# vcf-diode-ladder.net
KiCad netlist of a schematic drawn in EAGLE
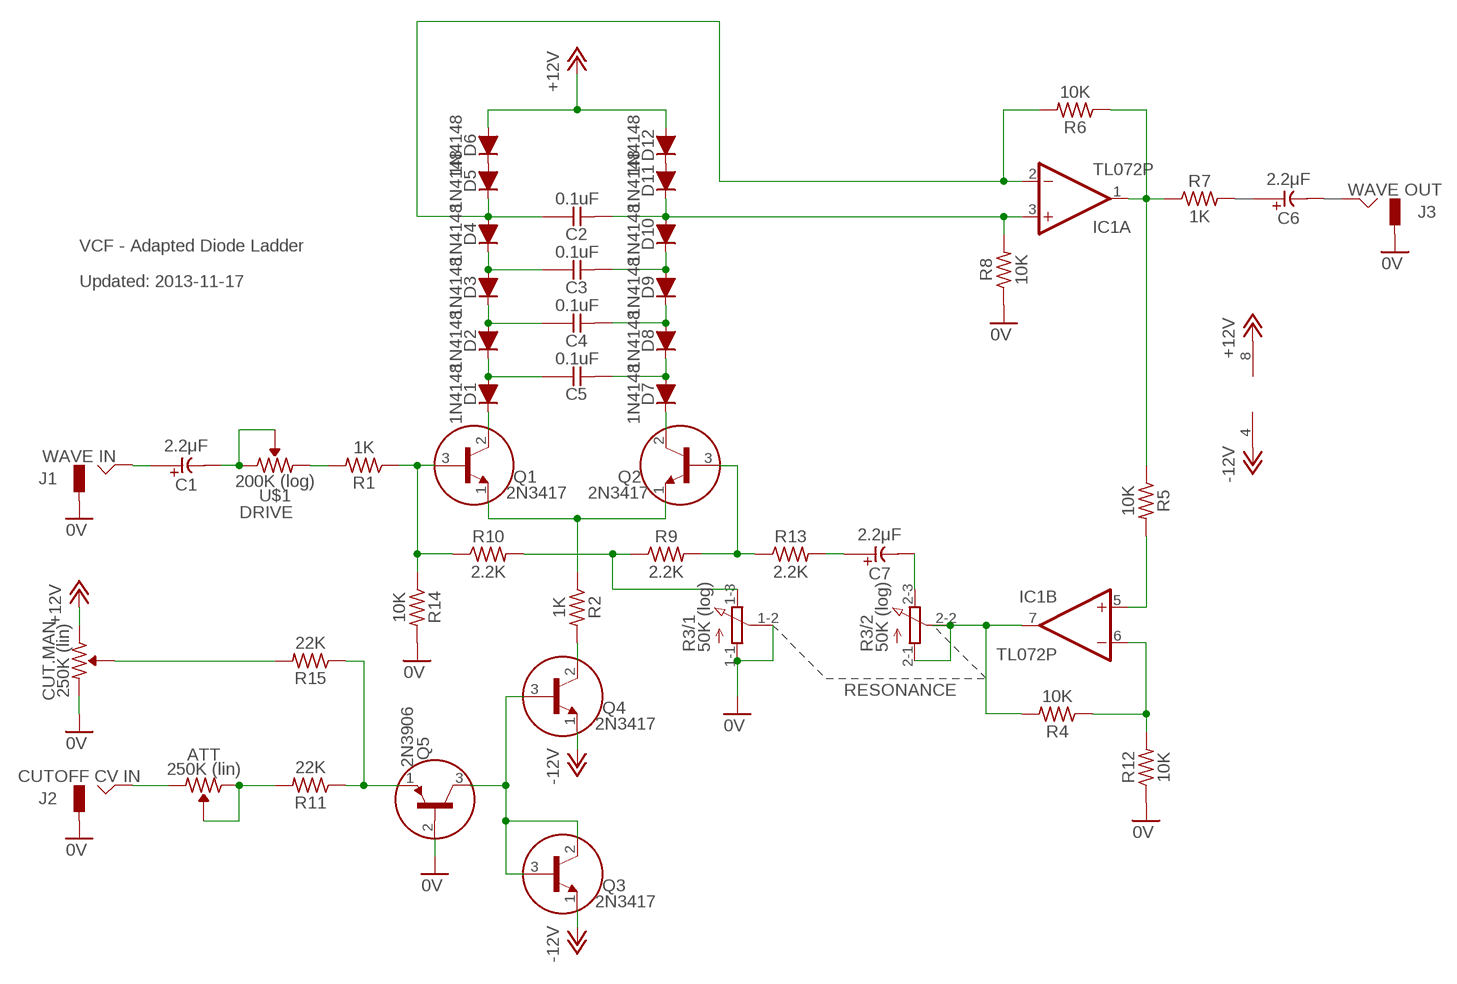
[diagram p0: schematic, sheet 1]

(export (version "E")
  (design (tool "Eeschema 10.0.6"))
  (components
    (comp (ref "ATT")
      (value "250K (lin)")
      (footprint "eagle-import:R-VAR")
      (libsource (lib "eagle-import") (part "R-VAR"))
    )
    (comp (ref "C1")
      (value "2.2μF")
      (footprint "eagle-import:E2-5")
      (libsource (lib "eagle-import") (part "CE-USE2-5"))
    )
    (comp (ref "C2")
      (value "0.1uF")
      (footprint "eagle-import:C025-024X044")
      (libsource (lib "eagle-import") (part "CC-US025-024X044"))
    )
    (comp (ref "C3")
      (value "0.1uF")
      (footprint "eagle-import:C025-024X044")
      (libsource (lib "eagle-import") (part "CC-US025-024X044"))
    )
    (comp (ref "C4")
      (value "0.1uF")
      (footprint "eagle-import:C025-024X044")
      (libsource (lib "eagle-import") (part "CC-US025-024X044"))
    )
    (comp (ref "C5")
      (value "0.1uF")
      (footprint "eagle-import:C025-024X044")
      (libsource (lib "eagle-import") (part "CC-US025-024X044"))
    )
    (comp (ref "C6")
      (value "2.2μF")
      (footprint "eagle-import:E2-5")
      (libsource (lib "eagle-import") (part "CE-USE2-5"))
    )
    (comp (ref "C7")
      (value "2.2μF")
      (footprint "eagle-import:E2-5")
      (libsource (lib "eagle-import") (part "CE-USE2-5"))
    )
    (comp (ref "CUT.MAN")
      (value "250K (lin)")
      (footprint "eagle-import:R-VAR")
      (libsource (lib "eagle-import") (part "R-VAR"))
    )
    (comp (ref "D1")
      (value "1N4148")
      (footprint "eagle-import:DO35-7")
      (libsource (lib "eagle-import") (part "1N4148"))
    )
    (comp (ref "D2")
      (value "1N4148")
      (footprint "eagle-import:DO35-7")
      (libsource (lib "eagle-import") (part "1N4148"))
    )
    (comp (ref "D3")
      (value "1N4148")
      (footprint "eagle-import:DO35-7")
      (libsource (lib "eagle-import") (part "1N4148"))
    )
    (comp (ref "D4")
      (value "1N4148")
      (footprint "eagle-import:DO35-7")
      (libsource (lib "eagle-import") (part "1N4148"))
    )
    (comp (ref "D5")
      (value "1N4148")
      (footprint "eagle-import:DO35-7")
      (libsource (lib "eagle-import") (part "1N4148"))
    )
    (comp (ref "D6")
      (value "1N4148")
      (footprint "eagle-import:DO35-7")
      (libsource (lib "eagle-import") (part "1N4148"))
    )
    (comp (ref "D7")
      (value "1N4148")
      (footprint "eagle-import:DO35-7")
      (libsource (lib "eagle-import") (part "1N4148"))
    )
    (comp (ref "D8")
      (value "1N4148")
      (footprint "eagle-import:DO35-7")
      (libsource (lib "eagle-import") (part "1N4148"))
    )
    (comp (ref "D9")
      (value "1N4148")
      (footprint "eagle-import:DO35-7")
      (libsource (lib "eagle-import") (part "1N4148"))
    )
    (comp (ref "D10")
      (value "1N4148")
      (footprint "eagle-import:DO35-7")
      (libsource (lib "eagle-import") (part "1N4148"))
    )
    (comp (ref "D11")
      (value "1N4148")
      (footprint "eagle-import:DO35-7")
      (libsource (lib "eagle-import") (part "1N4148"))
    )
    (comp (ref "D12")
      (value "1N4148")
      (footprint "eagle-import:DO35-7")
      (libsource (lib "eagle-import") (part "1N4148"))
    )
    (comp (ref "IC1")
      (value "TL072P")
      (footprint "eagle-import:DIL08")
      (libsource (lib "eagle-import") (part "TL072P"))
    )
    (comp (ref "J1")
      (value "WAVE IN")
      (footprint "eagle-import:JACK-M")
      (libsource (lib "eagle-import") (part "JACK-M"))
    )
    (comp (ref "J2")
      (value "CUTOFF CV IN")
      (footprint "eagle-import:JACK-M")
      (libsource (lib "eagle-import") (part "JACK-M"))
    )
    (comp (ref "J3")
      (value "WAVE OUT")
      (footprint "eagle-import:JACK-M")
      (libsource (lib "eagle-import") (part "JACK-M"))
    )
    (comp (ref "Q1")
      (value "2N3417")
      (footprint "eagle-import:TO92")
      (libsource (lib "eagle-import") (part "2N3417"))
    )
    (comp (ref "Q2")
      (value "2N3417")
      (footprint "eagle-import:TO92")
      (libsource (lib "eagle-import") (part "2N3417"))
    )
    (comp (ref "Q3")
      (value "2N3417")
      (footprint "eagle-import:TO92")
      (libsource (lib "eagle-import") (part "2N3417"))
    )
    (comp (ref "Q4")
      (value "2N3417")
      (footprint "eagle-import:TO92")
      (libsource (lib "eagle-import") (part "2N3417"))
    )
    (comp (ref "Q5")
      (value "2N3906")
      (footprint "eagle-import:TO92")
      (libsource (lib "eagle-import") (part "2N3906"))
    )
    (comp (ref "R1")
      (value "1K")
      (footprint "eagle-import:0309_10")
      (libsource (lib "eagle-import") (part "R0309/10"))
    )
    (comp (ref "R2")
      (value "1K")
      (footprint "eagle-import:0309_10")
      (libsource (lib "eagle-import") (part "R0309/10"))
    )
    (comp (ref "R3")
      (value "50K (log)")
      (footprint "eagle-import:3RP_1610G")
      (libsource (lib "eagle-import") (part "3RP/1610G"))
    )
    (comp (ref "R4")
      (value "10K")
      (footprint "eagle-import:0309_10")
      (libsource (lib "eagle-import") (part "R0309/10"))
    )
    (comp (ref "R5")
      (value "10K")
      (footprint "eagle-import:0309_10")
      (libsource (lib "eagle-import") (part "R0309/10"))
    )
    (comp (ref "R6")
      (value "10K")
      (footprint "eagle-import:0309_10")
      (libsource (lib "eagle-import") (part "R0309/10"))
    )
    (comp (ref "R7")
      (value "1K")
      (footprint "eagle-import:0309_10")
      (libsource (lib "eagle-import") (part "R0309/10"))
    )
    (comp (ref "R8")
      (value "10K")
      (footprint "eagle-import:0309_10")
      (libsource (lib "eagle-import") (part "R0309/10"))
    )
    (comp (ref "R9")
      (value "2.2K")
      (footprint "eagle-import:0309_10")
      (libsource (lib "eagle-import") (part "R0309/10"))
    )
    (comp (ref "R10")
      (value "2.2K")
      (footprint "eagle-import:0309_10")
      (libsource (lib "eagle-import") (part "R0309/10"))
    )
    (comp (ref "R11")
      (value "22K")
      (footprint "eagle-import:0309_10")
      (libsource (lib "eagle-import") (part "R0309/10"))
    )
    (comp (ref "R12")
      (value "10K")
      (footprint "eagle-import:0309_10")
      (libsource (lib "eagle-import") (part "R0309/10"))
    )
    (comp (ref "R13")
      (value "2.2K")
      (footprint "eagle-import:0309_10")
      (libsource (lib "eagle-import") (part "R0309/10"))
    )
    (comp (ref "R14")
      (value "10K")
      (footprint "eagle-import:0309_10")
      (libsource (lib "eagle-import") (part "R0309/10"))
    )
    (comp (ref "R15")
      (value "22K")
      (footprint "eagle-import:0309_10")
      (libsource (lib "eagle-import") (part "R0309/10"))
    )
    (comp (ref "U$1")
      (value "200K (log)")
      (footprint "eagle-import:R-VAR")
      (libsource (lib "eagle-import") (part "R-VAR"))
    )
  )
  (nets
    (net (code "1") (name "+12V") (class "Default")
      (node (ref "CUT.MAN") (pin "R1") (pinfunction "1_R1") (pintype "passive"))
      (node (ref "D12") (pin "A") (pinfunction "A_A") (pintype "passive"))
      (node (ref "D6") (pin "A") (pinfunction "A_A") (pintype "passive"))
      (node (ref "IC1") (pin "8") (pinfunction "V+_8") (pintype "power_in"))
    )
    (net (code "2") (name "-12V") (class "Default")
      (node (ref "IC1") (pin "4") (pinfunction "V-_4") (pintype "power_in"))
      (node (ref "Q3") (pin "1") (pinfunction "E_1") (pintype "passive"))
      (node (ref "Q4") (pin "1") (pinfunction "E_1") (pintype "passive"))
    )
    (net (code "3") (name "0V") (class "Default")
      (node (ref "CUT.MAN") (pin "R2") (pinfunction "2_R2") (pintype "passive"))
      (node (ref "J1") (pin "GND") (pinfunction "GND_GND") (pintype "bidirectional"))
      (node (ref "J2") (pin "GND") (pinfunction "GND_GND") (pintype "bidirectional"))
      (node (ref "J3") (pin "GND") (pinfunction "GND_GND") (pintype "bidirectional"))
      (node (ref "Q5") (pin "2") (pinfunction "B_2") (pintype "passive"))
      (node (ref "R12") (pin "1") (pinfunction "1_1") (pintype "passive"))
      (node (ref "R14") (pin "2") (pinfunction "2_2") (pintype "passive"))
      (node (ref "R3") (pin "1-1") (pinfunction "A_1-1") (pintype "passive"))
      (node (ref "R3") (pin "1-2") (pinfunction "S_1-2") (pintype "passive"))
      (node (ref "R8") (pin "1") (pinfunction "1_1") (pintype "passive"))
    )
    (net (code "4") (name "Net-(ATT-1)") (class "Default")
      (node (ref "ATT") (pin "R1") (pinfunction "1_R1") (pintype "passive"))
      (node (ref "ATT") (pin "VAR") (pinfunction "P$1_VAR") (pintype "passive"))
      (node (ref "R11") (pin "2") (pinfunction "2_2") (pintype "passive"))
    )
    (net (code "5") (name "Net-(ATT-2)") (class "Default")
      (node (ref "ATT") (pin "R2") (pinfunction "2_R2") (pintype "passive"))
      (node (ref "J2") (pin "HOT") (pinfunction "HOT_HOT") (pintype "bidirectional"))
    )
    (net (code "6") (name "Net-(C1-Pad+)") (class "Default")
      (node (ref "C1") (pin "+") (pinfunction "+_+") (pintype "passive"))
      (node (ref "J1") (pin "HOT") (pinfunction "HOT_HOT") (pintype "bidirectional"))
    )
    (net (code "7") (name "Net-(C3-Pad1)") (class "Default")
      (node (ref "C3") (pin "1") (pinfunction "1_1") (pintype "passive"))
      (node (ref "D3") (pin "A") (pinfunction "A_A") (pintype "passive"))
      (node (ref "D4") (pin "C") (pinfunction "C_C") (pintype "passive"))
    )
    (net (code "8") (name "Net-(C3-Pad2)") (class "Default")
      (node (ref "C3") (pin "2") (pinfunction "2_2") (pintype "passive"))
      (node (ref "D10") (pin "C") (pinfunction "C_C") (pintype "passive"))
      (node (ref "D9") (pin "A") (pinfunction "A_A") (pintype "passive"))
    )
    (net (code "9") (name "Net-(C4-Pad1)") (class "Default")
      (node (ref "C4") (pin "1") (pinfunction "1_1") (pintype "passive"))
      (node (ref "D2") (pin "A") (pinfunction "A_A") (pintype "passive"))
      (node (ref "D3") (pin "C") (pinfunction "C_C") (pintype "passive"))
    )
    (net (code "10") (name "Net-(C4-Pad2)") (class "Default")
      (node (ref "C4") (pin "2") (pinfunction "2_2") (pintype "passive"))
      (node (ref "D8") (pin "A") (pinfunction "A_A") (pintype "passive"))
      (node (ref "D9") (pin "C") (pinfunction "C_C") (pintype "passive"))
    )
    (net (code "11") (name "Net-(C5-Pad1)") (class "Default")
      (node (ref "C5") (pin "1") (pinfunction "1_1") (pintype "passive"))
      (node (ref "D1") (pin "A") (pinfunction "A_A") (pintype "passive"))
      (node (ref "D2") (pin "C") (pinfunction "C_C") (pintype "passive"))
    )
    (net (code "12") (name "Net-(C5-Pad2)") (class "Default")
      (node (ref "C5") (pin "2") (pinfunction "2_2") (pintype "passive"))
      (node (ref "D7") (pin "A") (pinfunction "A_A") (pintype "passive"))
      (node (ref "D8") (pin "C") (pinfunction "C_C") (pintype "passive"))
    )
    (net (code "13") (name "Net-(C7-Pad+)") (class "Default")
      (node (ref "C7") (pin "+") (pinfunction "+_+") (pintype "passive"))
      (node (ref "R13") (pin "2") (pinfunction "2_2") (pintype "passive"))
    )
    (net (code "14") (name "Net-(CUT.MAN-P$1)") (class "Default")
      (node (ref "CUT.MAN") (pin "VAR") (pinfunction "P$1_VAR") (pintype "passive"))
      (node (ref "R15") (pin "2") (pinfunction "2_2") (pintype "passive"))
    )
    (net (code "15") (name "Net-(D5-PadA)") (class "Default")
      (node (ref "D5") (pin "A") (pinfunction "A_A") (pintype "passive"))
      (node (ref "D6") (pin "C") (pinfunction "C_C") (pintype "passive"))
    )
    (net (code "16") (name "Net-(D11-PadA)") (class "Default")
      (node (ref "D11") (pin "A") (pinfunction "A_A") (pintype "passive"))
      (node (ref "D12") (pin "C") (pinfunction "C_C") (pintype "passive"))
    )
    (net (code "17") (name "Net-(IC1A-+IN)") (class "Default")
      (node (ref "C2") (pin "2") (pinfunction "2_2") (pintype "passive"))
      (node (ref "D10") (pin "A") (pinfunction "A_A") (pintype "passive"))
      (node (ref "D11") (pin "C") (pinfunction "C_C") (pintype "passive"))
      (node (ref "IC1") (pin "3") (pinfunction "+IN_3") (pintype "input"))
      (node (ref "R8") (pin "2") (pinfunction "2_2") (pintype "passive"))
    )
    (net (code "18") (name "Net-(IC1A--IN)") (class "Default")
      (node (ref "C2") (pin "1") (pinfunction "1_1") (pintype "passive"))
      (node (ref "D4") (pin "A") (pinfunction "A_A") (pintype "passive"))
      (node (ref "D5") (pin "C") (pinfunction "C_C") (pintype "passive"))
      (node (ref "IC1") (pin "2") (pinfunction "-IN_2") (pintype "input"))
      (node (ref "R6") (pin "2") (pinfunction "2_2") (pintype "passive"))
    )
    (net (code "19") (name "Net-(IC1A-OUT)") (class "Default")
      (node (ref "IC1") (pin "1") (pinfunction "OUT_1") (pintype "output"))
      (node (ref "R5") (pin "1") (pinfunction "1_1") (pintype "passive"))
      (node (ref "R6") (pin "1") (pinfunction "1_1") (pintype "passive"))
      (node (ref "R7") (pin "1") (pinfunction "1_1") (pintype "passive"))
    )
    (net (code "20") (name "Net-(IC1B-+IN)") (class "Default")
      (node (ref "IC1") (pin "5") (pinfunction "+IN_5") (pintype "input"))
      (node (ref "R5") (pin "2") (pinfunction "2_2") (pintype "passive"))
    )
    (net (code "21") (name "Net-(IC1B--IN)") (class "Default")
      (node (ref "IC1") (pin "6") (pinfunction "-IN_6") (pintype "input"))
      (node (ref "R12") (pin "2") (pinfunction "2_2") (pintype "passive"))
      (node (ref "R4") (pin "1") (pinfunction "1_1") (pintype "passive"))
    )
    (net (code "22") (name "Net-(IC1B-OUT)") (class "Default")
      (node (ref "IC1") (pin "7") (pinfunction "OUT_7") (pintype "output"))
      (node (ref "R3") (pin "2-1") (pinfunction "A_2-1") (pintype "passive"))
      (node (ref "R3") (pin "2-2") (pinfunction "S_2-2") (pintype "passive"))
      (node (ref "R4") (pin "2") (pinfunction "2_2") (pintype "passive"))
    )
    (net (code "23") (name "Net-(Q1-B)") (class "Default")
      (node (ref "Q1") (pin "3") (pinfunction "B_3") (pintype "passive"))
      (node (ref "R1") (pin "1") (pinfunction "1_1") (pintype "passive"))
      (node (ref "R10") (pin "1") (pinfunction "1_1") (pintype "passive"))
      (node (ref "R14") (pin "1") (pinfunction "1_1") (pintype "passive"))
    )
    (net (code "24") (name "Net-(Q1-C)") (class "Default")
      (node (ref "D1") (pin "C") (pinfunction "C_C") (pintype "passive"))
      (node (ref "Q1") (pin "2") (pinfunction "C_2") (pintype "passive"))
    )
    (net (code "25") (name "Net-(Q1-E)") (class "Default")
      (node (ref "Q1") (pin "1") (pinfunction "E_1") (pintype "passive"))
      (node (ref "Q2") (pin "1") (pinfunction "E_1") (pintype "passive"))
      (node (ref "R2") (pin "1") (pinfunction "1_1") (pintype "passive"))
    )
    (net (code "26") (name "Net-(Q2-B)") (class "Default")
      (node (ref "Q2") (pin "3") (pinfunction "B_3") (pintype "passive"))
      (node (ref "R13") (pin "1") (pinfunction "1_1") (pintype "passive"))
      (node (ref "R9") (pin "2") (pinfunction "2_2") (pintype "passive"))
    )
    (net (code "27") (name "Net-(Q2-C)") (class "Default")
      (node (ref "D7") (pin "C") (pinfunction "C_C") (pintype "passive"))
      (node (ref "Q2") (pin "2") (pinfunction "C_2") (pintype "passive"))
    )
    (net (code "28") (name "Net-(Q3-B)") (class "Default")
      (node (ref "Q3") (pin "2") (pinfunction "C_2") (pintype "passive"))
      (node (ref "Q3") (pin "3") (pinfunction "B_3") (pintype "passive"))
      (node (ref "Q4") (pin "3") (pinfunction "B_3") (pintype "passive"))
      (node (ref "Q5") (pin "3") (pinfunction "C_3") (pintype "passive"))
    )
    (net (code "29") (name "Net-(Q4-C)") (class "Default")
      (node (ref "Q4") (pin "2") (pinfunction "C_2") (pintype "passive"))
      (node (ref "R2") (pin "2") (pinfunction "2_2") (pintype "passive"))
    )
    (net (code "30") (name "Net-(Q5-E)") (class "Default")
      (node (ref "Q5") (pin "1") (pinfunction "E_1") (pintype "passive"))
      (node (ref "R11") (pin "1") (pinfunction "1_1") (pintype "passive"))
      (node (ref "R15") (pin "1") (pinfunction "1_1") (pintype "passive"))
    )
    (net (code "31") (name "Net-(R3A-E)") (class "Default")
      (node (ref "R10") (pin "2") (pinfunction "2_2") (pintype "passive"))
      (node (ref "R3") (pin "1-3") (pinfunction "E_1-3") (pintype "passive"))
      (node (ref "R9") (pin "1") (pinfunction "1_1") (pintype "passive"))
    )
    (net (code "32") (name "Net-(R3B-E)") (class "Default")
      (node (ref "C7") (pin "-") (pinfunction "-_-") (pintype "passive"))
      (node (ref "R3") (pin "2-3") (pinfunction "E_2-3") (pintype "passive"))
    )
    (net (code "33") (name "Net-(U$1-1)") (class "Default")
      (node (ref "C1") (pin "-") (pinfunction "-_-") (pintype "passive"))
      (node (ref "U$1") (pin "R1") (pinfunction "1_R1") (pintype "passive"))
      (node (ref "U$1") (pin "VAR") (pinfunction "P$1_VAR") (pintype "passive"))
    )
    (net (code "34") (name "Net-(U$1-2)") (class "Default")
      (node (ref "R1") (pin "2") (pinfunction "2_2") (pintype "passive"))
      (node (ref "U$1") (pin "R2") (pinfunction "2_R2") (pintype "passive"))
    )
    (net (code "35") (name "unconnected-(C6-Pad+)") (class "Default")
      (node (ref "C6") (pin "+") (pinfunction "+_+") (pintype "passive"))
    )
    (net (code "36") (name "unconnected-(C6-Pad-)") (class "Default")
      (node (ref "C6") (pin "-") (pinfunction "-_-") (pintype "passive"))
    )
    (net (code "37") (name "unconnected-(J3-PadHOT)") (class "Default")
      (node (ref "J3") (pin "HOT") (pinfunction "HOT_HOT") (pintype "bidirectional"))
    )
    (net (code "38") (name "unconnected-(R7-Pad2)") (class "Default")
      (node (ref "R7") (pin "2") (pinfunction "2_2") (pintype "passive"))
    )
  )
)
